# dac-board.net
KiCad netlist of a schematic drawn in EAGLE
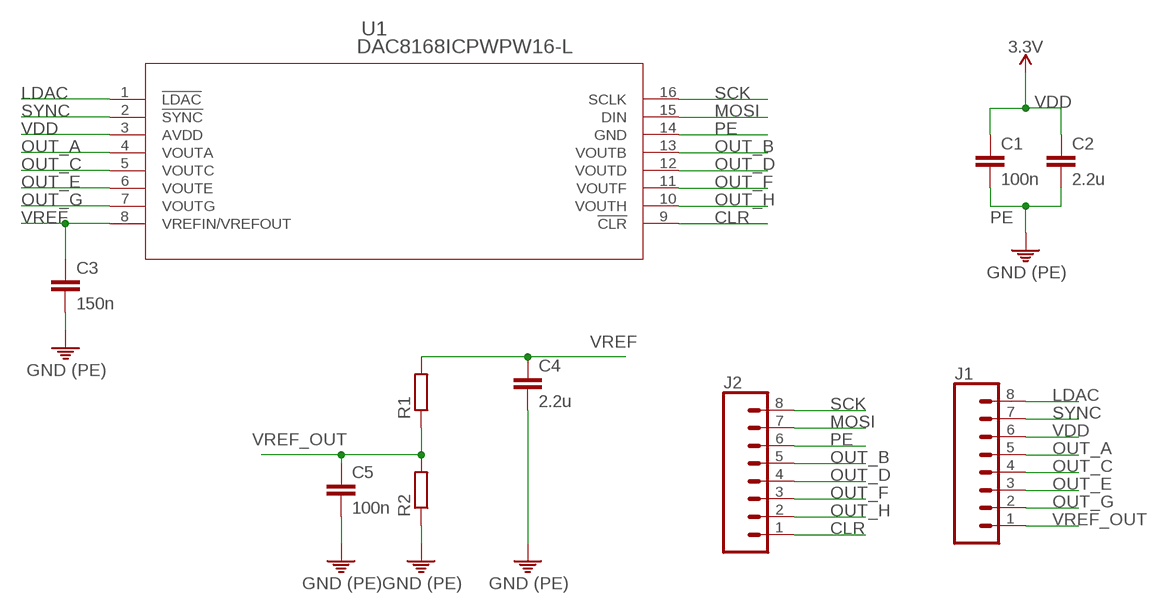
[diagram p0: schematic, sheet 1]

(export (version "E")
  (design (tool "Eeschema 10.0.6"))
  (components
    (comp (ref "C1")
      (value "100n")
      (footprint "eagle-import:C0603")
      (libsource (lib "eagle-import") (part "CAPACITOR-EUC0603"))
    )
    (comp (ref "C2")
      (value "2.2u")
      (footprint "eagle-import:C0805")
      (libsource (lib "eagle-import") (part "CAPACITOR-EUC0805"))
    )
    (comp (ref "C3")
      (value "150n")
      (footprint "eagle-import:C0603")
      (libsource (lib "eagle-import") (part "CAPACITOR-EUC0603"))
    )
    (comp (ref "C4")
      (value "2.2u")
      (footprint "eagle-import:C0805")
      (libsource (lib "eagle-import") (part "CAPACITOR-EUC0805"))
    )
    (comp (ref "C5")
      (value "100n")
      (footprint "eagle-import:C0603")
      (libsource (lib "eagle-import") (part "CAPACITOR-EUC0603"))
    )
    (comp (ref "J1")
      (value "CONN_08LOCK")
      (footprint "eagle-import:1X08_LOCK")
      (libsource (lib "eagle-import") (part "CONN_08LOCK"))
    )
    (comp (ref "J2")
      (value "CONN_08LOCK")
      (footprint "eagle-import:1X08_LOCK")
      (libsource (lib "eagle-import") (part "CONN_08LOCK"))
    )
    (comp (ref "R1")
      (value "RESISTOR-EU_R0603")
      (footprint "eagle-import:R0603")
      (libsource (lib "eagle-import") (part "RESISTOR-EU_R0603"))
    )
    (comp (ref "R2")
      (value "RESISTOR-EU_R0603")
      (footprint "eagle-import:R0603")
      (libsource (lib "eagle-import") (part "RESISTOR-EU_R0603"))
    )
    (comp (ref "U1")
      (value "DAC8168ICPWPW16-L")
      (footprint "eagle-import:PW16-L")
      (fields (field (name "MANUFACTURER_PART_NUMBER") "DAC8168ICPW"))
      (libsource (lib "eagle-import") (part "DAC8168ICPWPW16-L"))
    )
  )
  (nets
    (net (code "1") (name "/CLR") (class "Default")
      (node (ref "J2") (pin "1") (pinfunction "1_1") (pintype "passive"))
      (node (ref "U1") (pin "9") (pinfunction "~{CLR}_9") (pintype "input"))
    )
    (net (code "2") (name "/LDAC") (class "Default")
      (node (ref "J1") (pin "8") (pinfunction "8_8") (pintype "passive"))
      (node (ref "U1") (pin "1") (pinfunction "~{LDAC}_1") (pintype "passive"))
    )
    (net (code "3") (name "/MOSI") (class "Default")
      (node (ref "J2") (pin "7") (pinfunction "7_7") (pintype "passive"))
      (node (ref "U1") (pin "15") (pinfunction "DIN_15") (pintype "input"))
    )
    (net (code "4") (name "/OUT_A") (class "Default")
      (node (ref "J1") (pin "5") (pinfunction "5_5") (pintype "passive"))
      (node (ref "U1") (pin "4") (pinfunction "VOUTA_4") (pintype "output"))
    )
    (net (code "5") (name "/OUT_B") (class "Default")
      (node (ref "J2") (pin "5") (pinfunction "5_5") (pintype "passive"))
      (node (ref "U1") (pin "13") (pinfunction "VOUTB_13") (pintype "output"))
    )
    (net (code "6") (name "/OUT_C") (class "Default")
      (node (ref "J1") (pin "4") (pinfunction "4_4") (pintype "passive"))
      (node (ref "U1") (pin "5") (pinfunction "VOUTC_5") (pintype "output"))
    )
    (net (code "7") (name "/OUT_D") (class "Default")
      (node (ref "J2") (pin "4") (pinfunction "4_4") (pintype "passive"))
      (node (ref "U1") (pin "12") (pinfunction "VOUTD_12") (pintype "output"))
    )
    (net (code "8") (name "/OUT_E") (class "Default")
      (node (ref "J1") (pin "3") (pinfunction "3_3") (pintype "passive"))
      (node (ref "U1") (pin "6") (pinfunction "VOUTE_6") (pintype "output"))
    )
    (net (code "9") (name "/OUT_F") (class "Default")
      (node (ref "J2") (pin "3") (pinfunction "3_3") (pintype "passive"))
      (node (ref "U1") (pin "11") (pinfunction "VOUTF_11") (pintype "output"))
    )
    (net (code "10") (name "/OUT_G") (class "Default")
      (node (ref "J1") (pin "2") (pinfunction "2_2") (pintype "passive"))
      (node (ref "U1") (pin "7") (pinfunction "VOUTG_7") (pintype "output"))
    )
    (net (code "11") (name "/OUT_H") (class "Default")
      (node (ref "J2") (pin "2") (pinfunction "2_2") (pintype "passive"))
      (node (ref "U1") (pin "10") (pinfunction "VOUTH_10") (pintype "output"))
    )
    (net (code "12") (name "/SCK") (class "Default")
      (node (ref "J2") (pin "8") (pinfunction "8_8") (pintype "passive"))
      (node (ref "U1") (pin "16") (pinfunction "SCLK_16") (pintype "input"))
    )
    (net (code "13") (name "/SYNC") (class "Default")
      (node (ref "J1") (pin "7") (pinfunction "7_7") (pintype "passive"))
      (node (ref "U1") (pin "2") (pinfunction "~{SYNC}_2") (pintype "input"))
    )
    (net (code "14") (name "/VREF") (class "Default")
      (node (ref "C3") (pin "1") (pinfunction "1_1") (pintype "passive"))
      (node (ref "C4") (pin "1") (pinfunction "1_1") (pintype "passive"))
      (node (ref "R1") (pin "2") (pinfunction "2_2") (pintype "passive"))
      (node (ref "U1") (pin "8") (pinfunction "VREFIN/VREFOUT_8") (pintype "bidirectional"))
    )
    (net (code "15") (name "/VREF_OUT") (class "Default")
      (node (ref "C5") (pin "1") (pinfunction "1_1") (pintype "passive"))
      (node (ref "J1") (pin "1") (pinfunction "1_1") (pintype "passive"))
      (node (ref "R1") (pin "1") (pinfunction "1_1") (pintype "passive"))
      (node (ref "R2") (pin "2") (pinfunction "2_2") (pintype "passive"))
    )
    (net (code "16") (name "3.3V") (class "Default")
      (node (ref "C1") (pin "1") (pinfunction "1_1") (pintype "passive"))
      (node (ref "C2") (pin "1") (pinfunction "1_1") (pintype "passive"))
      (node (ref "J1") (pin "6") (pinfunction "6_6") (pintype "passive"))
      (node (ref "U1") (pin "3") (pinfunction "AVDD_3") (pintype "power_in"))
    )
    (net (code "17") (name "POWER-GND") (class "Default")
      (node (ref "C1") (pin "2") (pinfunction "2_2") (pintype "passive"))
      (node (ref "C2") (pin "2") (pinfunction "2_2") (pintype "passive"))
      (node (ref "C3") (pin "2") (pinfunction "2_2") (pintype "passive"))
      (node (ref "C4") (pin "2") (pinfunction "2_2") (pintype "passive"))
      (node (ref "C5") (pin "2") (pinfunction "2_2") (pintype "passive"))
      (node (ref "J2") (pin "6") (pinfunction "6_6") (pintype "passive"))
      (node (ref "R2") (pin "1") (pinfunction "1_1") (pintype "passive"))
      (node (ref "U1") (pin "14") (pinfunction "GND_14") (pintype "power_in"))
    )
  )
)
